# logger_lambda_new2.net
KiCad netlist of a schematic drawn in EAGLE
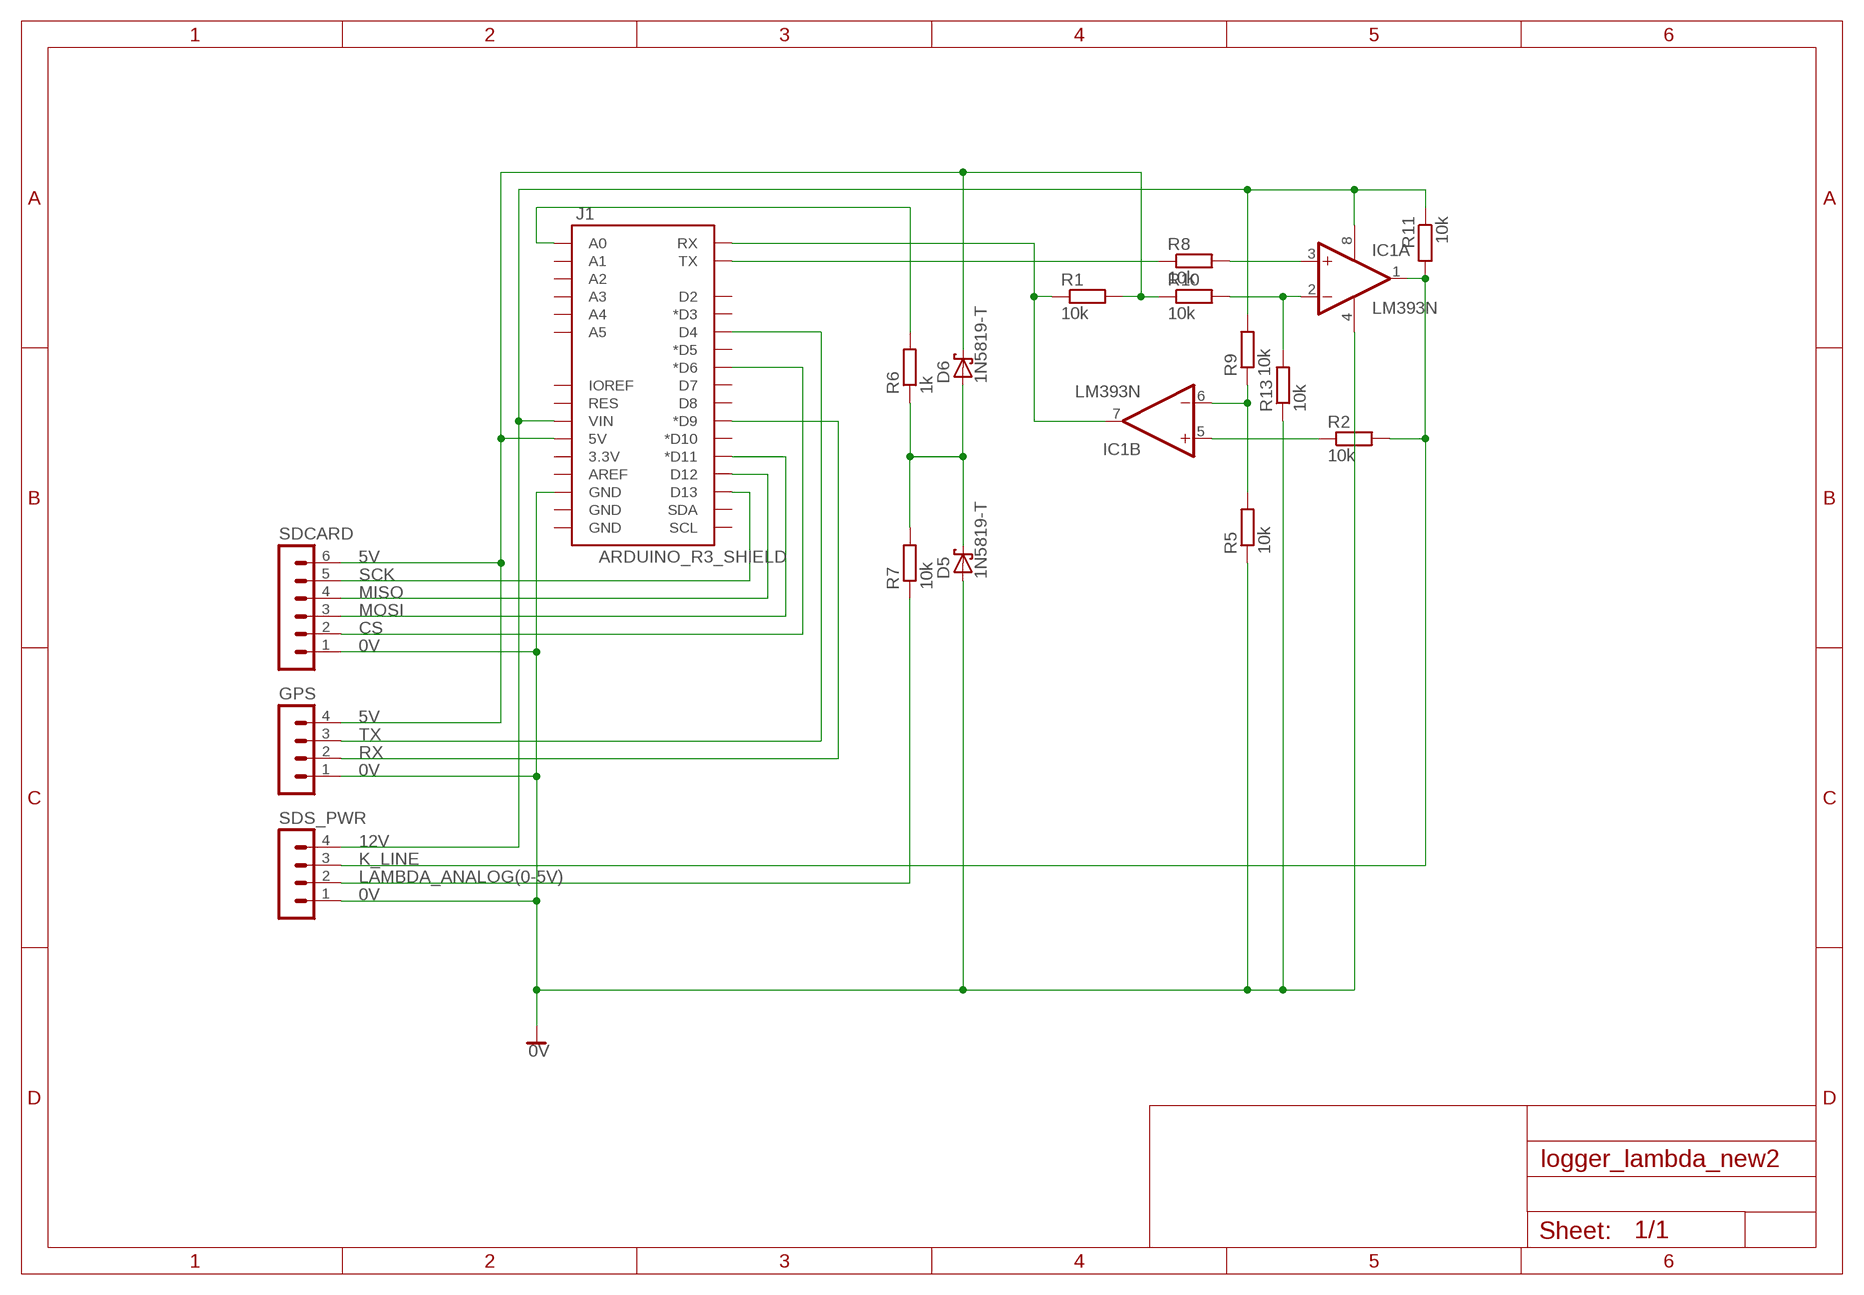
[diagram p0: schematic, sheet 1]

(export (version "E")
  (design (tool "Eeschema 10.0.6"))
  (components
    (comp (ref "D5")
      (value "1N5819-T")
      (footprint "eagle-import:DO41-7.6")
      (libsource (lib "eagle-import") (part "1N5819-T"))
    )
    (comp (ref "D6")
      (value "1N5819-T")
      (footprint "eagle-import:DO41-7.6")
      (libsource (lib "eagle-import") (part "1N5819-T"))
    )
    (comp (ref "GPS")
      (value "MA04-1")
      (footprint "eagle-import:MA04-1")
      (libsource (lib "eagle-import") (part "MA04-1"))
    )
    (comp (ref "IC1")
      (value "LM393N")
      (footprint "eagle-import:DIL08")
      (libsource (lib "eagle-import") (part "LM393N"))
    )
    (comp (ref "J1")
      (value "ARDUINO_R3_SHIELD")
      (footprint "eagle-import:UNO_R3_SHIELD")
      (libsource (lib "eagle-import") (part "ARDUINO_R3_SHIELD"))
    )
    (comp (ref "R1")
      (value "10k")
      (footprint "eagle-import:0207_7")
      (libsource (lib "eagle-import") (part "R-EU_0207/7"))
    )
    (comp (ref "R2")
      (value "10k")
      (footprint "eagle-import:0207_7")
      (libsource (lib "eagle-import") (part "R-EU_0207/7"))
    )
    (comp (ref "R5")
      (value "10k")
      (footprint "eagle-import:0207_7")
      (libsource (lib "eagle-import") (part "R-EU_0207/7"))
    )
    (comp (ref "R6")
      (value "1k")
      (footprint "eagle-import:0207_7")
      (libsource (lib "eagle-import") (part "R-EU_0207/7"))
    )
    (comp (ref "R7")
      (value "10k")
      (footprint "eagle-import:0207_7")
      (libsource (lib "eagle-import") (part "R-EU_0207/7"))
    )
    (comp (ref "R8")
      (value "10k")
      (footprint "eagle-import:0207_7")
      (libsource (lib "eagle-import") (part "R-EU_0207/7"))
    )
    (comp (ref "R9")
      (value "10k")
      (footprint "eagle-import:0207_7")
      (libsource (lib "eagle-import") (part "R-EU_0207/7"))
    )
    (comp (ref "R10")
      (value "10k")
      (footprint "eagle-import:0207_7")
      (libsource (lib "eagle-import") (part "R-EU_0207/7"))
    )
    (comp (ref "R11")
      (value "10k")
      (footprint "eagle-import:0207_7")
      (libsource (lib "eagle-import") (part "R-EU_0207/7"))
    )
    (comp (ref "R13")
      (value "10k")
      (footprint "eagle-import:0207_7")
      (libsource (lib "eagle-import") (part "R-EU_0207/7"))
    )
    (comp (ref "SDCARD")
      (value "MA06-1")
      (footprint "eagle-import:MA06-1")
      (libsource (lib "eagle-import") (part "MA06-1"))
    )
    (comp (ref "SDS_PWR")
      (value "MA04-1")
      (footprint "eagle-import:MA04-1")
      (libsource (lib "eagle-import") (part "MA04-1"))
    )
  )
  (nets
    (net (code "1") (name "/5V") (class "Default")
      (node (ref "D6") (pin "C") (pinfunction "C_C") (pintype "passive"))
      (node (ref "GPS") (pin "4") (pinfunction "4_4") (pintype "passive"))
      (node (ref "J1") (pin "5V") (pinfunction "5V_5V") (pintype "bidirectional"))
      (node (ref "R1") (pin "2") (pinfunction "2_2") (pintype "passive"))
      (node (ref "R10") (pin "1") (pinfunction "1_1") (pintype "passive"))
      (node (ref "SDCARD") (pin "6") (pinfunction "6_6") (pintype "passive"))
    )
    (net (code "2") (name "/12V") (class "Default")
      (node (ref "IC1") (pin "8") (pinfunction "V+_8") (pintype "power_in"))
      (node (ref "J1") (pin "VIN") (pinfunction "VIN_VIN") (pintype "bidirectional"))
      (node (ref "R11") (pin "1") (pinfunction "1_1") (pintype "passive"))
      (node (ref "R9") (pin "2") (pinfunction "2_2") (pintype "passive"))
      (node (ref "SDS_PWR") (pin "4") (pinfunction "4_4") (pintype "passive"))
    )
    (net (code "3") (name "/ANALOG_IN") (class "Default")
      (node (ref "D5") (pin "C") (pinfunction "C_C") (pintype "passive"))
      (node (ref "D6") (pin "A") (pinfunction "A_A") (pintype "passive"))
      (node (ref "J1") (pin "A0") (pinfunction "A0_A0") (pintype "bidirectional"))
      (node (ref "R6") (pin "1") (pinfunction "1_1") (pintype "passive"))
      (node (ref "R6") (pin "2") (pinfunction "2_2") (pintype "passive"))
      (node (ref "R7") (pin "2") (pinfunction "2_2") (pintype "passive"))
    )
    (net (code "4") (name "/CS") (class "Default")
      (node (ref "J1") (pin "D6") (pinfunction "*D6_D6") (pintype "bidirectional"))
      (node (ref "SDCARD") (pin "2") (pinfunction "2_2") (pintype "passive"))
    )
    (net (code "5") (name "/K_LINE") (class "Default")
      (node (ref "IC1") (pin "1") (pinfunction "OUT_1") (pintype "output"))
      (node (ref "R11") (pin "2") (pinfunction "2_2") (pintype "passive"))
      (node (ref "R2") (pin "2") (pinfunction "2_2") (pintype "passive"))
      (node (ref "SDS_PWR") (pin "3") (pinfunction "3_3") (pintype "passive"))
    )
    (net (code "6") (name "/LAMBDA_ANALOG(0-5V)") (class "Default")
      (node (ref "R7") (pin "1") (pinfunction "1_1") (pintype "passive"))
      (node (ref "SDS_PWR") (pin "2") (pinfunction "2_2") (pintype "passive"))
    )
    (net (code "7") (name "/MISO") (class "Default")
      (node (ref "J1") (pin "D12") (pinfunction "D12_D12") (pintype "bidirectional"))
      (node (ref "SDCARD") (pin "4") (pinfunction "4_4") (pintype "passive"))
    )
    (net (code "8") (name "/MOSI") (class "Default")
      (node (ref "J1") (pin "D11") (pinfunction "*D11_D11") (pintype "bidirectional"))
      (node (ref "SDCARD") (pin "3") (pinfunction "3_3") (pintype "passive"))
    )
    (net (code "9") (name "/RX") (class "Default")
      (node (ref "GPS") (pin "2") (pinfunction "2_2") (pintype "passive"))
      (node (ref "J1") (pin "D9") (pinfunction "*D9_D9") (pintype "bidirectional"))
    )
    (net (code "10") (name "/SCK") (class "Default")
      (node (ref "J1") (pin "D13") (pinfunction "D13_D13") (pintype "bidirectional"))
      (node (ref "SDCARD") (pin "5") (pinfunction "5_5") (pintype "passive"))
    )
    (net (code "11") (name "/TX") (class "Default")
      (node (ref "GPS") (pin "3") (pinfunction "3_3") (pintype "passive"))
      (node (ref "J1") (pin "D4") (pinfunction "D4_D4") (pintype "bidirectional"))
    )
    (net (code "12") (name "0V") (class "Default")
      (node (ref "D5") (pin "A") (pinfunction "A_A") (pintype "passive"))
      (node (ref "GPS") (pin "1") (pinfunction "1_1") (pintype "passive"))
      (node (ref "IC1") (pin "4") (pinfunction "V-_4") (pintype "power_in"))
      (node (ref "J1") (pin "GND@2") (pinfunction "GND_GND@2") (pintype "bidirectional"))
      (node (ref "R13") (pin "1") (pinfunction "1_1") (pintype "passive"))
      (node (ref "R5") (pin "1") (pinfunction "1_1") (pintype "passive"))
      (node (ref "SDCARD") (pin "1") (pinfunction "1_1") (pintype "passive"))
      (node (ref "SDS_PWR") (pin "1") (pinfunction "1_1") (pintype "passive"))
    )
    (net (code "13") (name "Net-(IC1A-+IN)") (class "Default")
      (node (ref "IC1") (pin "3") (pinfunction "+IN_3") (pintype "input"))
      (node (ref "R8") (pin "2") (pinfunction "2_2") (pintype "passive"))
    )
    (net (code "14") (name "Net-(IC1A--IN)") (class "Default")
      (node (ref "IC1") (pin "2") (pinfunction "-IN_2") (pintype "input"))
      (node (ref "R10") (pin "2") (pinfunction "2_2") (pintype "passive"))
      (node (ref "R13") (pin "2") (pinfunction "2_2") (pintype "passive"))
    )
    (net (code "15") (name "Net-(IC1B-+IN)") (class "Default")
      (node (ref "IC1") (pin "5") (pinfunction "+IN_5") (pintype "input"))
      (node (ref "R2") (pin "1") (pinfunction "1_1") (pintype "passive"))
    )
    (net (code "16") (name "Net-(IC1B--IN)") (class "Default")
      (node (ref "IC1") (pin "6") (pinfunction "-IN_6") (pintype "input"))
      (node (ref "R5") (pin "2") (pinfunction "2_2") (pintype "passive"))
      (node (ref "R9") (pin "1") (pinfunction "1_1") (pintype "passive"))
    )
    (net (code "17") (name "Net-(IC1B-OUT)") (class "Default")
      (node (ref "IC1") (pin "7") (pinfunction "OUT_7") (pintype "output"))
      (node (ref "J1") (pin "RX") (pinfunction "RX_RX") (pintype "bidirectional"))
      (node (ref "R1") (pin "1") (pinfunction "1_1") (pintype "passive"))
    )
    (net (code "18") (name "Net-(J1-PadTX)") (class "Default")
      (node (ref "J1") (pin "TX") (pinfunction "TX_TX") (pintype "bidirectional"))
      (node (ref "R8") (pin "1") (pinfunction "1_1") (pintype "passive"))
    )
    (net (code "19") (name "unconnected-(J1-*D3-PadD3)") (class "Default")
      (node (ref "J1") (pin "D3") (pinfunction "*D3_D3") (pintype "bidirectional"))
    )
    (net (code "20") (name "unconnected-(J1-*D5-PadD5)") (class "Default")
      (node (ref "J1") (pin "D5") (pinfunction "*D5_D5") (pintype "bidirectional"))
    )
    (net (code "21") (name "unconnected-(J1-*D10-PadD10)") (class "Default")
      (node (ref "J1") (pin "D10") (pinfunction "*D10_D10") (pintype "bidirectional"))
    )
    (net (code "22") (name "unconnected-(J1-GND-PadGND@0)") (class "Default")
      (node (ref "J1") (pin "GND@0") (pinfunction "GND_GND@0") (pintype "bidirectional"))
    )
    (net (code "23") (name "unconnected-(J1-GND-PadGND@1)") (class "Default")
      (node (ref "J1") (pin "GND@1") (pinfunction "GND_GND@1") (pintype "bidirectional"))
    )
    (net (code "24") (name "unconnected-(J1-Pad3.3V)") (class "Default")
      (node (ref "J1") (pin "3.3V") (pinfunction "3.3V_3.3V") (pintype "bidirectional"))
    )
    (net (code "25") (name "unconnected-(J1-PadA1)") (class "Default")
      (node (ref "J1") (pin "A1") (pinfunction "A1_A1") (pintype "bidirectional"))
    )
    (net (code "26") (name "unconnected-(J1-PadA2)") (class "Default")
      (node (ref "J1") (pin "A2") (pinfunction "A2_A2") (pintype "bidirectional"))
    )
    (net (code "27") (name "unconnected-(J1-PadA3)") (class "Default")
      (node (ref "J1") (pin "A3") (pinfunction "A3_A3") (pintype "bidirectional"))
    )
    (net (code "28") (name "unconnected-(J1-PadA4)") (class "Default")
      (node (ref "J1") (pin "A4") (pinfunction "A4_A4") (pintype "bidirectional"))
    )
    (net (code "29") (name "unconnected-(J1-PadA5)") (class "Default")
      (node (ref "J1") (pin "A5") (pinfunction "A5_A5") (pintype "bidirectional"))
    )
    (net (code "30") (name "unconnected-(J1-PadAREF)") (class "Default")
      (node (ref "J1") (pin "AREF") (pinfunction "AREF_AREF") (pintype "bidirectional"))
    )
    (net (code "31") (name "unconnected-(J1-PadD2)") (class "Default")
      (node (ref "J1") (pin "D2") (pinfunction "D2_D2") (pintype "bidirectional"))
    )
    (net (code "32") (name "unconnected-(J1-PadD7)") (class "Default")
      (node (ref "J1") (pin "D7") (pinfunction "D7_D7") (pintype "bidirectional"))
    )
    (net (code "33") (name "unconnected-(J1-PadD8)") (class "Default")
      (node (ref "J1") (pin "D8") (pinfunction "D8_D8") (pintype "bidirectional"))
    )
    (net (code "34") (name "unconnected-(J1-PadIOREF)") (class "Default")
      (node (ref "J1") (pin "IOREF") (pinfunction "IOREF_IOREF") (pintype "bidirectional"))
    )
    (net (code "35") (name "unconnected-(J1-PadRES)") (class "Default")
      (node (ref "J1") (pin "RES") (pinfunction "RES_RES") (pintype "bidirectional"))
    )
    (net (code "36") (name "unconnected-(J1-PadSCL)") (class "Default")
      (node (ref "J1") (pin "SCL") (pinfunction "SCL_SCL") (pintype "bidirectional"))
    )
    (net (code "37") (name "unconnected-(J1-PadSDA)") (class "Default")
      (node (ref "J1") (pin "SDA") (pinfunction "SDA_SDA") (pintype "bidirectional"))
    )
  )
)
